# design.net
KiCad netlist of a schematic drawn in Altium Designer
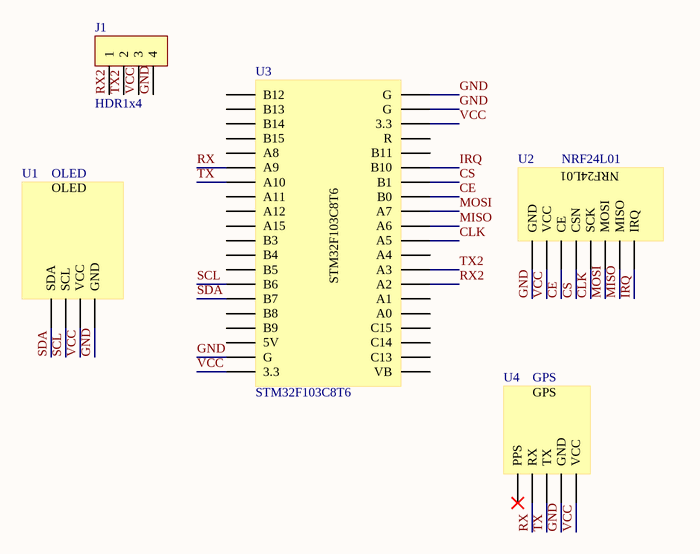
[diagram p0: 毕设.SchDoc]

(export (version "E")
  (design (tool "Eeschema 10.0.6"))
  (components
    (comp (ref "J1")
      (value "HDR1x4")
      (footprint "PIN-4-2.54-1.0")
      (description "Connector")
      (libsource (lib "General") (part "HDR1x4"))
    )
    (comp (ref "U1") (value "OLED") (footprint "OLED") (libsource (lib "毕设原理图库") (part "OLED")))
    (comp (ref "U2") (value "NRF24L01") (footprint "NRF24L01") (libsource (lib "毕设原理图库") (part "NRF24L01")))
    (comp (ref "U3")
      (value "STM32F103C8T6")
      (footprint "STM32F103C8T6")
      (libsource (lib "毕设原理图库") (part "STM32F103C8T6"))
    )
    (comp (ref "U4") (value "GPS") (footprint "GPS") (libsource (lib "毕设原理图库") (part "GPS")))
  )
  (nets
    (net (code "1") (name "/CE") (class "Default")
      (node (ref "U2") (pin "3") (pinfunction "CE_3") (pintype "passive"))
      (node (ref "U3") (pin "13") (pinfunction "B0_13") (pintype "passive"))
    )
    (net (code "2") (name "/CLK") (class "Default")
      (node (ref "U2") (pin "5") (pinfunction "SCK_5") (pintype "passive"))
      (node (ref "U3") (pin "10") (pinfunction "A5_10") (pintype "passive"))
    )
    (net (code "3") (name "/CS") (class "Default")
      (node (ref "U2") (pin "4") (pinfunction "CSN_4") (pintype "passive"))
      (node (ref "U3") (pin "14") (pinfunction "B1_14") (pintype "passive"))
    )
    (net (code "4") (name "/GND") (class "Default")
      (node (ref "J1") (pin "4") (pinfunction "4_4") (pintype "passive"))
      (node (ref "U1") (pin "4") (pinfunction "GND_4") (pintype "passive"))
      (node (ref "U2") (pin "1") (pinfunction "GND_1") (pintype "passive"))
      (node (ref "U3") (pin "19") (pinfunction "G_19") (pintype "passive"))
      (node (ref "U3") (pin "20") (pinfunction "G_20") (pintype "passive"))
      (node (ref "U3") (pin "22") (pinfunction "G_22") (pintype "passive"))
      (node (ref "U4") (pin "4") (pinfunction "GND_4") (pintype "passive"))
    )
    (net (code "5") (name "/IRQ") (class "Default")
      (node (ref "U2") (pin "8") (pinfunction "IRQ_8") (pintype "passive"))
      (node (ref "U3") (pin "15") (pinfunction "B10_15") (pintype "passive"))
    )
    (net (code "6") (name "/MISO") (class "Default")
      (node (ref "U2") (pin "7") (pinfunction "MISO_7") (pintype "passive"))
      (node (ref "U3") (pin "11") (pinfunction "A6_11") (pintype "passive"))
    )
    (net (code "7") (name "/MOSI") (class "Default")
      (node (ref "U2") (pin "6") (pinfunction "MOSI_6") (pintype "passive"))
      (node (ref "U3") (pin "12") (pinfunction "A7_12") (pintype "passive"))
    )
    (net (code "8") (name "/RX") (class "Default")
      (node (ref "U3") (pin "35") (pinfunction "A9_35") (pintype "passive"))
      (node (ref "U4") (pin "2") (pinfunction "RX_2") (pintype "passive"))
    )
    (net (code "9") (name "/RX2") (class "Default")
      (node (ref "J1") (pin "1") (pinfunction "1_1") (pintype "passive"))
      (node (ref "U3") (pin "7") (pinfunction "A2_7") (pintype "passive"))
    )
    (net (code "10") (name "/SCL") (class "Default")
      (node (ref "U1") (pin "2") (pinfunction "SCL_2") (pintype "passive"))
      (node (ref "U3") (pin "27") (pinfunction "B6_27") (pintype "passive"))
    )
    (net (code "11") (name "/SDA") (class "Default")
      (node (ref "U1") (pin "1") (pinfunction "SDA_1") (pintype "passive"))
      (node (ref "U3") (pin "26") (pinfunction "B7_26") (pintype "passive"))
    )
    (net (code "12") (name "/TX") (class "Default")
      (node (ref "U3") (pin "34") (pinfunction "A10_34") (pintype "passive"))
      (node (ref "U4") (pin "3") (pinfunction "TX_3") (pintype "passive"))
    )
    (net (code "13") (name "/TX2") (class "Default")
      (node (ref "J1") (pin "2") (pinfunction "2_2") (pintype "passive"))
      (node (ref "U3") (pin "8") (pinfunction "A3_8") (pintype "passive"))
    )
    (net (code "14") (name "/VCC") (class "Default")
      (node (ref "J1") (pin "3") (pinfunction "3_3") (pintype "passive"))
      (node (ref "U1") (pin "3") (pinfunction "VCC_3") (pintype "passive"))
      (node (ref "U2") (pin "2") (pinfunction "VCC_2") (pintype "passive"))
      (node (ref "U3") (pin "18") (pinfunction "3.3_18") (pintype "passive"))
      (node (ref "U3") (pin "21") (pinfunction "3.3_21") (pintype "passive"))
      (node (ref "U4") (pin "5") (pinfunction "VCC_5") (pintype "passive"))
    )
    (net (code "15") (name "unconnected-(U3-5V-Pad23)") (class "Default")
      (node (ref "U3") (pin "23") (pinfunction "5V_23") (pintype "passive"))
    )
    (net (code "16") (name "unconnected-(U3-A0-Pad5)") (class "Default")
      (node (ref "U3") (pin "5") (pinfunction "A0_5") (pintype "passive"))
    )
    (net (code "17") (name "unconnected-(U3-A1-Pad6)") (class "Default")
      (node (ref "U3") (pin "6") (pinfunction "A1_6") (pintype "passive"))
    )
    (net (code "18") (name "unconnected-(U3-A4-Pad9)") (class "Default")
      (node (ref "U3") (pin "9") (pinfunction "A4_9") (pintype "passive"))
    )
    (net (code "19") (name "unconnected-(U3-A8-Pad36)") (class "Default")
      (node (ref "U3") (pin "36") (pinfunction "A8_36") (pintype "passive"))
    )
    (net (code "20") (name "unconnected-(U3-A11-Pad33)") (class "Default")
      (node (ref "U3") (pin "33") (pinfunction "A11_33") (pintype "passive"))
    )
    (net (code "21") (name "unconnected-(U3-A12-Pad32)") (class "Default")
      (node (ref "U3") (pin "32") (pinfunction "A12_32") (pintype "passive"))
    )
    (net (code "22") (name "unconnected-(U3-A15-Pad31)") (class "Default")
      (node (ref "U3") (pin "31") (pinfunction "A15_31") (pintype "passive"))
    )
    (net (code "23") (name "unconnected-(U3-B3-Pad30)") (class "Default")
      (node (ref "U3") (pin "30") (pinfunction "B3_30") (pintype "passive"))
    )
    (net (code "24") (name "unconnected-(U3-B4-Pad29)") (class "Default")
      (node (ref "U3") (pin "29") (pinfunction "B4_29") (pintype "passive"))
    )
    (net (code "25") (name "unconnected-(U3-B5-Pad28)") (class "Default")
      (node (ref "U3") (pin "28") (pinfunction "B5_28") (pintype "passive"))
    )
    (net (code "26") (name "unconnected-(U3-B8-Pad25)") (class "Default")
      (node (ref "U3") (pin "25") (pinfunction "B8_25") (pintype "passive"))
    )
    (net (code "27") (name "unconnected-(U3-B9-Pad24)") (class "Default")
      (node (ref "U3") (pin "24") (pinfunction "B9_24") (pintype "passive"))
    )
    (net (code "28") (name "unconnected-(U3-B11-Pad16)") (class "Default")
      (node (ref "U3") (pin "16") (pinfunction "B11_16") (pintype "passive"))
    )
    (net (code "29") (name "unconnected-(U3-B12-Pad40)") (class "Default")
      (node (ref "U3") (pin "40") (pinfunction "B12_40") (pintype "passive"))
    )
    (net (code "30") (name "unconnected-(U3-B13-Pad39)") (class "Default")
      (node (ref "U3") (pin "39") (pinfunction "B13_39") (pintype "passive"))
    )
    (net (code "31") (name "unconnected-(U3-B14-Pad38)") (class "Default")
      (node (ref "U3") (pin "38") (pinfunction "B14_38") (pintype "passive"))
    )
    (net (code "32") (name "unconnected-(U3-B15-Pad37)") (class "Default")
      (node (ref "U3") (pin "37") (pinfunction "B15_37") (pintype "passive"))
    )
    (net (code "33") (name "unconnected-(U3-C13-Pad2)") (class "Default")
      (node (ref "U3") (pin "2") (pinfunction "C13_2") (pintype "passive"))
    )
    (net (code "34") (name "unconnected-(U3-C14-Pad3)") (class "Default")
      (node (ref "U3") (pin "3") (pinfunction "C14_3") (pintype "passive"))
    )
    (net (code "35") (name "unconnected-(U3-C15-Pad4)") (class "Default")
      (node (ref "U3") (pin "4") (pinfunction "C15_4") (pintype "passive"))
    )
    (net (code "36") (name "unconnected-(U3-R-Pad17)") (class "Default")
      (node (ref "U3") (pin "17") (pinfunction "R_17") (pintype "passive"))
    )
    (net (code "37") (name "unconnected-(U3-VB-Pad1)") (class "Default")
      (node (ref "U3") (pin "1") (pinfunction "VB_1") (pintype "passive"))
    )
    (net (code "38") (name "unconnected-(U4-PPS-Pad1)") (class "Default")
      (node (ref "U4") (pin "1") (pinfunction "PPS_1") (pintype "passive+no_connect"))
    )
  )
)
